# LB_BIT_o1_LED-v02_rev1.net
KiCad netlist of a schematic drawn in EAGLE
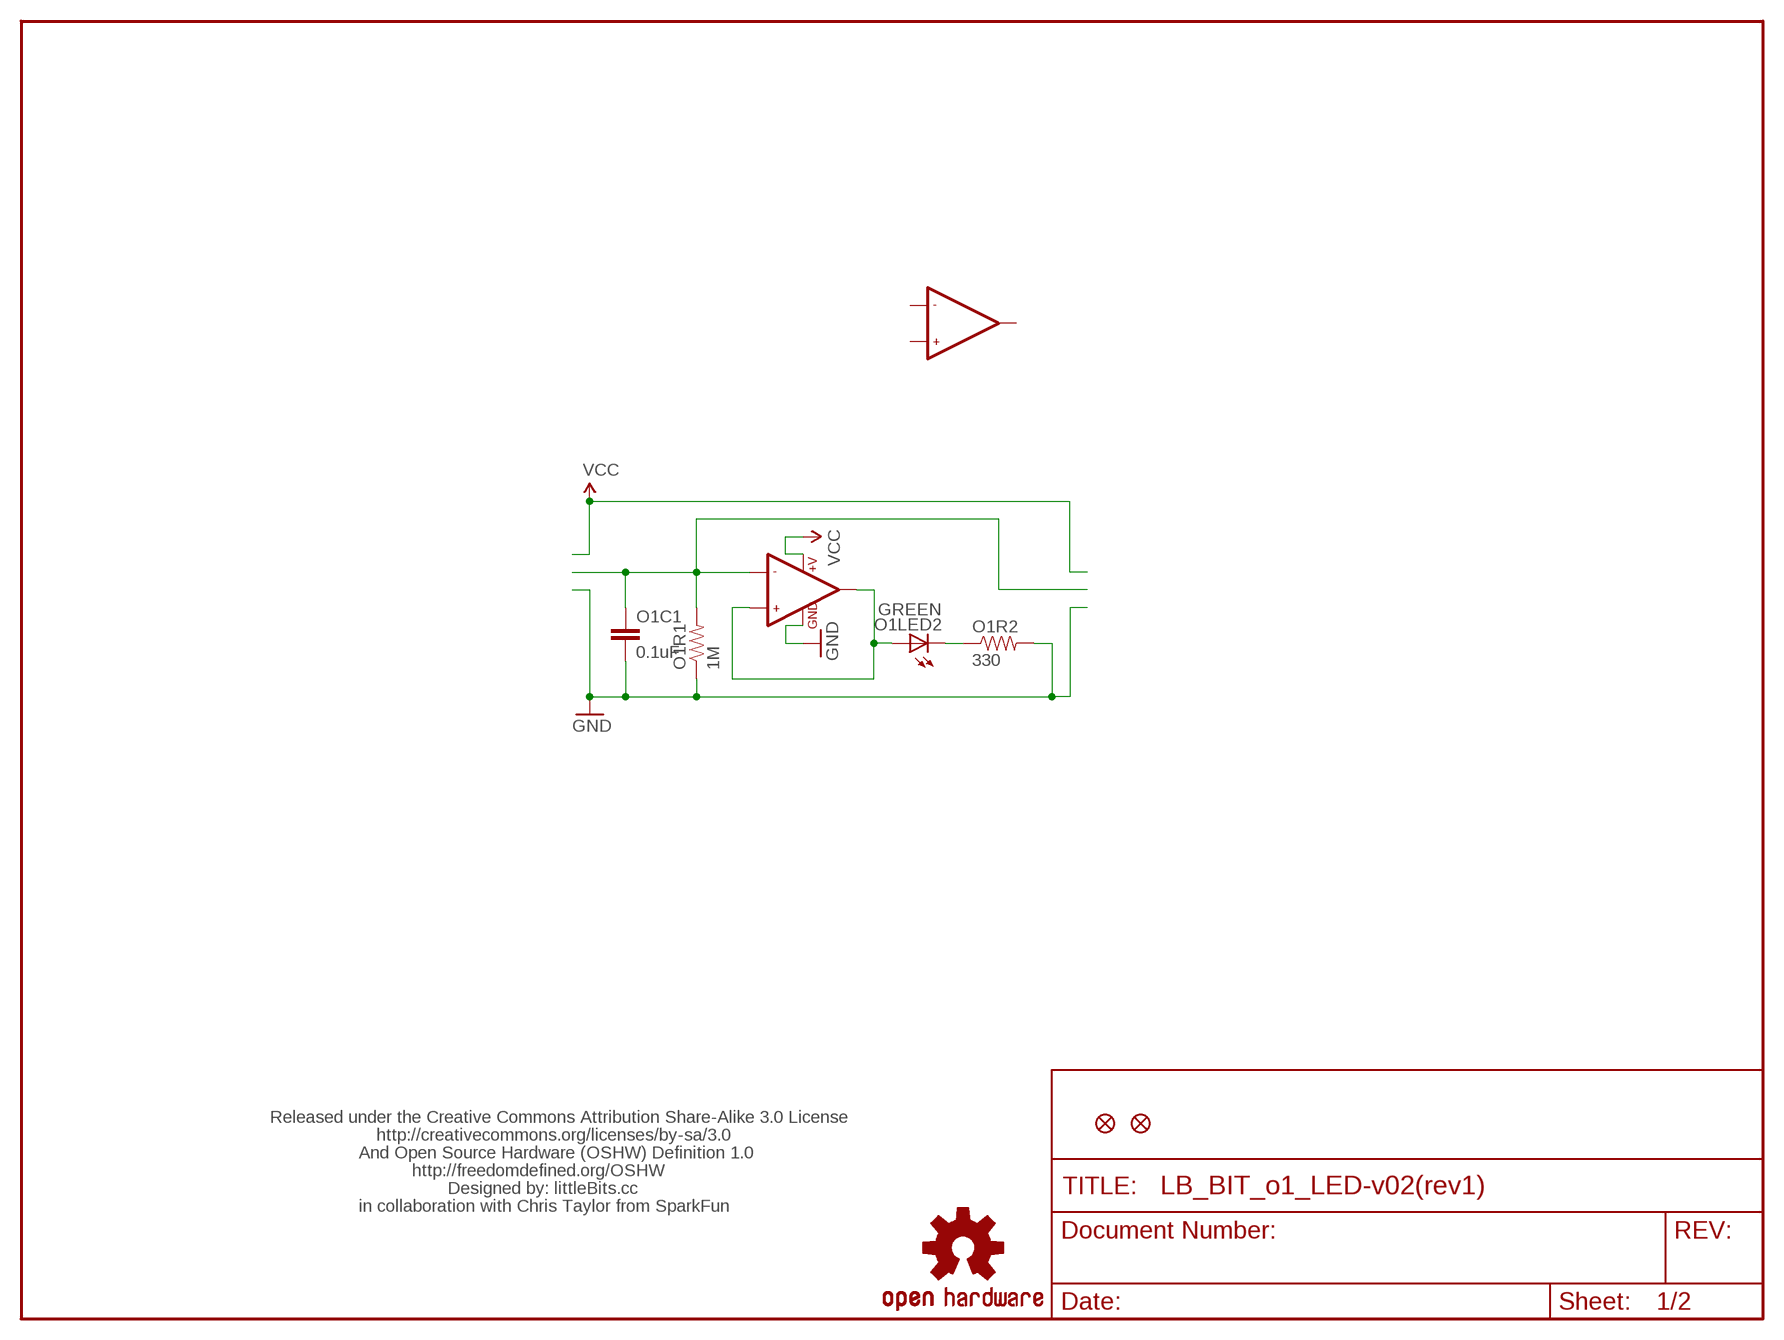
[diagram p0: schematic, sheet 1]
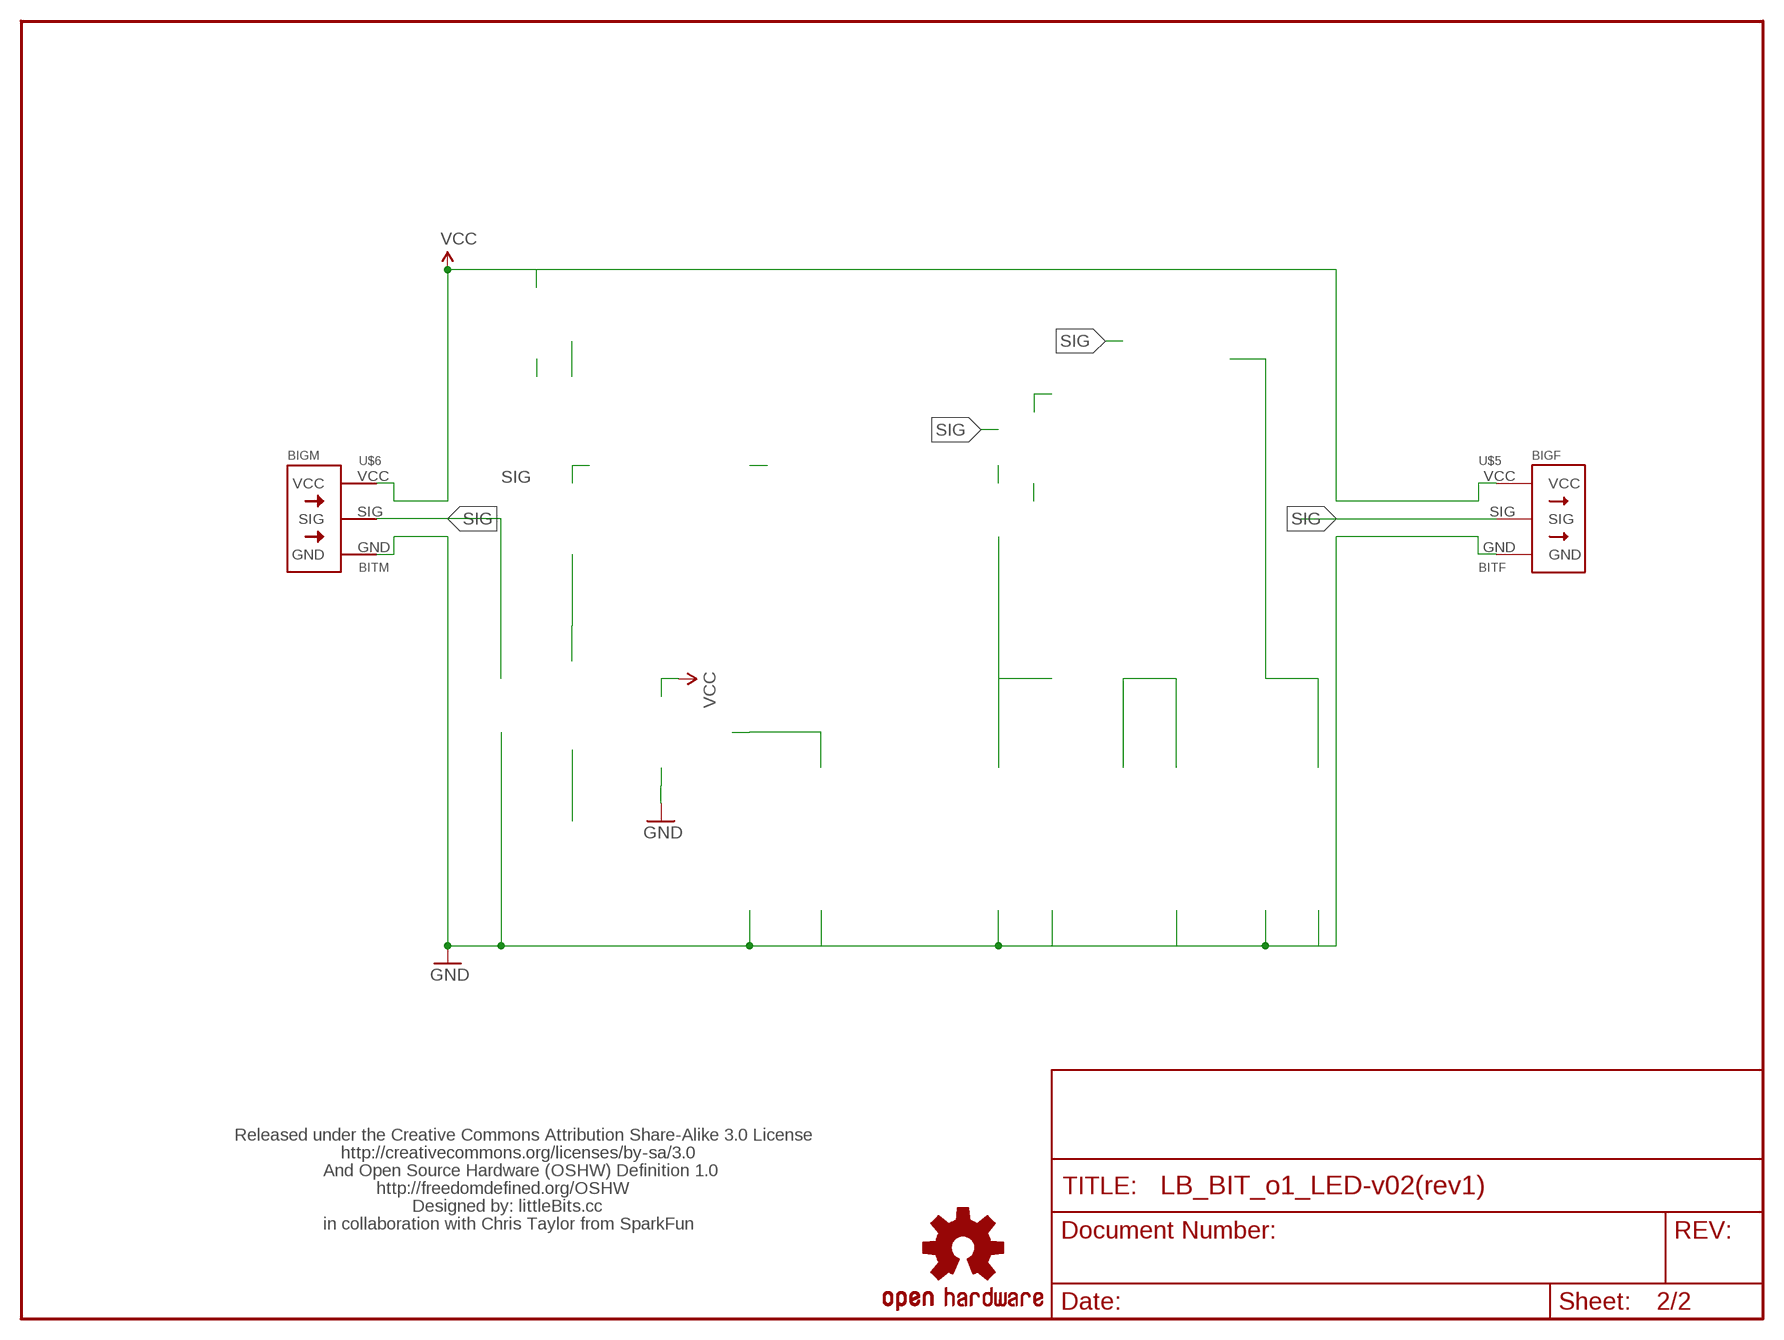
[diagram p1: schematic, sheet 2]

(export (version "E")
  (design (tool "Eeschema 10.0.6"))
  (components
    (comp (ref "JP1")
      (value "FIDUCIAL1X2.5")
      (footprint "eagle-import:FIDUCIAL-1X2.5")
      (libsource (lib "eagle-import") (part "FIDUCIAL1X2.5"))
    )
    (comp (ref "JP2")
      (value "FIDUCIAL1X2.5")
      (footprint "eagle-import:FIDUCIAL-1X2.5")
      (libsource (lib "eagle-import") (part "FIDUCIAL1X2.5"))
    )
    (comp (ref "O1C1")
      (value "0.1uF")
      (footprint "eagle-import:1206")
      (libsource (lib "eagle-import") (part "CAP1206"))
    )
    (comp (ref "O1LED2")
      (value "GREEN")
      (footprint "eagle-import:LED-1206")
      (libsource (lib "eagle-import") (part "LED1206"))
    )
    (comp (ref "O1R1")
      (value "1M")
      (footprint "eagle-import:0805")
      (libsource (lib "eagle-import") (part "RESISTOR"))
    )
    (comp (ref "O1R2")
      (value "330")
      (footprint "eagle-import:0805")
      (libsource (lib "eagle-import") (part "RESISTOR"))
    )
    (comp (ref "U$1")
      (value "LB_CREDITS")
      (footprint "eagle-import:OSHWCREDIT")
      (libsource (lib "eagle-import") (part "LB_CREDITS"))
    )
    (comp (ref "U$3")
      (value "OSHW-LOGOL")
      (footprint "eagle-import:OSHW-LOGO-L")
      (libsource (lib "eagle-import") (part "OSHW-LOGOL"))
    )
    (comp (ref "U$7")
      (value "LMV358")
      (footprint "eagle-import:SO08")
      (libsource (lib "eagle-import") (part "LMV358"))
    )
    (comp (ref "U$2")
      (value "OSHW-LOGOL")
      (footprint "eagle-import:OSHW-LOGO-L")
      (libsource (lib "eagle-import") (part "OSHW-LOGOL"))
    )
    (comp (ref "U$4")
      (value "LB_CREDITS")
      (footprint "eagle-import:OSHWCREDIT")
      (libsource (lib "eagle-import") (part "LB_CREDITS"))
    )
    (comp (ref "U$5")
      (value "BITF")
      (footprint "eagle-import:BITM")
      (libsource (lib "eagle-import") (part "BITF"))
    )
    (comp (ref "U$6")
      (value "BITM")
      (footprint "eagle-import:BITM")
      (libsource (lib "eagle-import") (part "BITM"))
    )
  )
  (nets
    (net (code "1") (name "GND") (class "Default")
      (node (ref "O1C1") (pin "2") (pinfunction "2_2") (pintype "passive"))
      (node (ref "O1R1") (pin "1") (pinfunction "1_1") (pintype "passive"))
      (node (ref "O1R2") (pin "2") (pinfunction "2_2") (pintype "passive"))
      (node (ref "U$5") (pin "GND") (pinfunction "GND_GND") (pintype "bidirectional"))
      (node (ref "U$6") (pin "GND") (pinfunction "GND_GND") (pintype "bidirectional"))
      (node (ref "U$7") (pin "4") (pinfunction "GND_4") (pintype "power_in"))
    )
    (net (code "2") (name "Net-(O1LED2-PadC)") (class "Default")
      (node (ref "O1LED2") (pin "C") (pinfunction "C_C") (pintype "passive"))
      (node (ref "O1R2") (pin "1") (pinfunction "1_1") (pintype "passive"))
    )
    (net (code "3") (name "Net-(U$7A-+IN1)") (class "Default")
      (node (ref "O1LED2") (pin "A") (pinfunction "A_A") (pintype "passive"))
      (node (ref "U$7") (pin "1") (pinfunction "OUT1_1") (pintype "output"))
      (node (ref "U$7") (pin "3") (pinfunction "+IN1_3") (pintype "input"))
    )
    (net (code "4") (name "SIG") (class "Default")
      (node (ref "O1C1") (pin "1") (pinfunction "1_1") (pintype "passive"))
      (node (ref "O1R1") (pin "2") (pinfunction "2_2") (pintype "passive"))
      (node (ref "U$5") (pin "SIG") (pinfunction "SIG_SIG") (pintype "bidirectional"))
      (node (ref "U$6") (pin "SIG") (pinfunction "SIG_SIG") (pintype "bidirectional"))
      (node (ref "U$7") (pin "2") (pinfunction "-IN1_2") (pintype "input"))
    )
    (net (code "5") (name "VCC") (class "Default")
      (node (ref "U$5") (pin "VCC") (pinfunction "VCC_VCC") (pintype "bidirectional"))
      (node (ref "U$6") (pin "VCC") (pinfunction "VCC_VCC") (pintype "bidirectional"))
      (node (ref "U$7") (pin "8") (pinfunction "+V_8") (pintype "power_in"))
    )
    (net (code "6") (name "unconnected-(U$7B-+IN2-Pad5)") (class "Default")
      (node (ref "U$7") (pin "5") (pinfunction "+IN2_5") (pintype "input"))
    )
    (net (code "7") (name "unconnected-(U$7B--IN2-Pad6)") (class "Default")
      (node (ref "U$7") (pin "6") (pinfunction "-IN2_6") (pintype "input"))
    )
    (net (code "8") (name "unconnected-(U$7B-OUT2-Pad7)") (class "Default")
      (node (ref "U$7") (pin "7") (pinfunction "OUT2_7") (pintype "output"))
    )
  )
)
